# Sheet5.net
KiCad netlist of a schematic drawn in Altium Designer
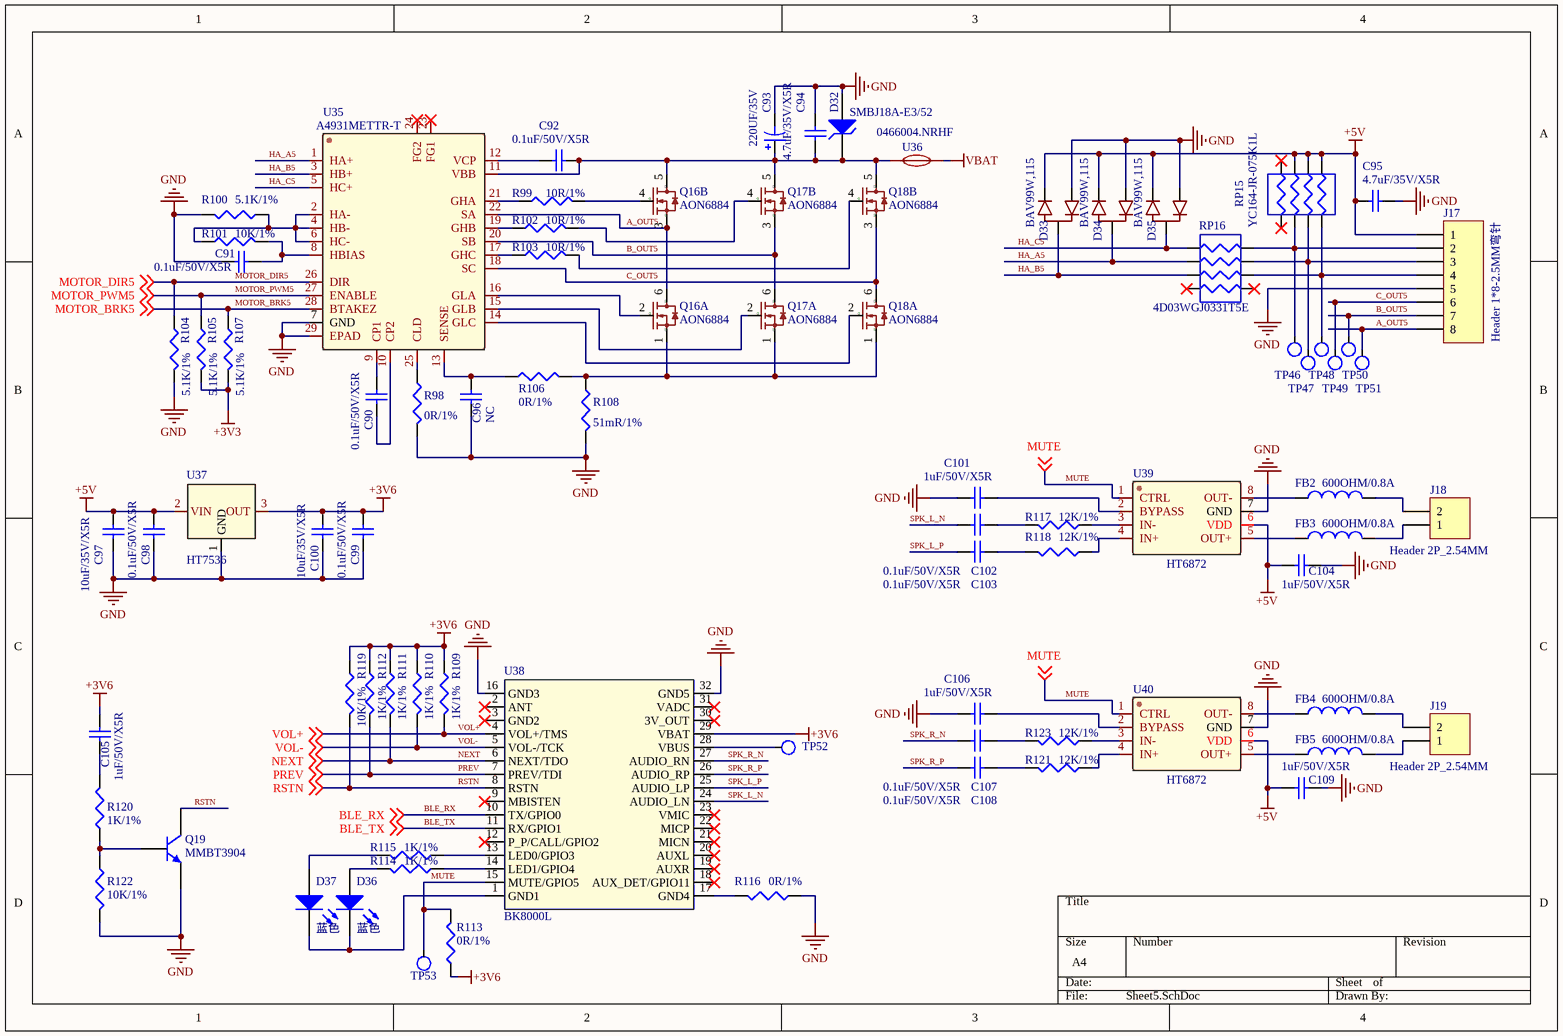
[diagram p0: Sheet5.SchDoc]

(export (version "E")
  (design (tool "Eeschema 10.0.6"))
  (components
    (comp (ref "C90")
      (value "0.1uF/50V/X5R")
      (footprint "C0603")
      (description "Capacitor (Semiconductor SIM Model)")
      (fields (field (name "PUBLISHER") "Altium Limited"))
      (libsource (lib "Miscellaneous Devices") (part "Cap Semi"))
    )
    (comp (ref "C91")
      (value "0.1uF/50V/X5R")
      (footprint "C0603")
      (description "Capacitor (Semiconductor SIM Model)")
      (fields (field (name "PUBLISHER") "Altium Limited"))
      (libsource (lib "Miscellaneous Devices") (part "Cap Semi"))
    )
    (comp (ref "C92")
      (value "0.1uF/50V/X5R")
      (footprint "C0603")
      (description "Capacitor (Semiconductor SIM Model)")
      (fields (field (name "PUBLISHER") "Altium Limited"))
      (libsource (lib "Miscellaneous Devices") (part "Cap Semi"))
    )
    (comp (ref "C93")
      (value "220UF/35V")
      (footprint "SMD_8X10.2")
      (description "Polarized Capacitor (Radial)")
      (fields (field (name "PUBLISHER") "Altium Limited"))
      (libsource (lib "Miscellaneous Devices") (part "Cap Pol1"))
    )
    (comp (ref "C94")
      (value "4.7uF/35V/X5R")
      (footprint "C0805")
      (description "Capacitor (Semiconductor SIM Model)")
      (fields (field (name "PUBLISHER") "Altium Limited"))
      (libsource (lib "Miscellaneous Devices") (part "Cap Semi"))
    )
    (comp (ref "C95")
      (value "4.7uF/35V/X5R")
      (footprint "C0603")
      (description "Capacitor (Semiconductor SIM Model)")
      (fields (field (name "PUBLISHER") "Altium Limited"))
      (libsource (lib "Miscellaneous Devices") (part "Cap Semi"))
    )
    (comp (ref "C96")
      (value "NC")
      (footprint "C0603")
      (description "Capacitor (Semiconductor SIM Model)")
      (fields (field (name "PUBLISHER") "Altium Limited"))
      (libsource (lib "Miscellaneous Devices") (part "Cap Semi"))
    )
    (comp (ref "C97")
      (value "10uF/35V/X5R")
      (footprint "C0805")
      (description "Capacitor (Semiconductor SIM Model)")
      (fields (field (name "PUBLISHER") "Altium Limited"))
      (libsource (lib "Miscellaneous Devices") (part "Cap Semi"))
    )
    (comp (ref "C98")
      (value "0.1uF/50V/X5R")
      (footprint "C0603")
      (description "Capacitor (Semiconductor SIM Model)")
      (fields (field (name "PUBLISHER") "Altium Limited"))
      (libsource (lib "Miscellaneous Devices") (part "Cap Semi"))
    )
    (comp (ref "C99")
      (value "0.1uF/50V/X5R")
      (footprint "C0603")
      (description "Capacitor (Semiconductor SIM Model)")
      (fields (field (name "PUBLISHER") "Altium Limited"))
      (libsource (lib "Miscellaneous Devices") (part "Cap Semi"))
    )
    (comp (ref "C100")
      (value "10uF/35V/X5R")
      (footprint "C0805")
      (description "Capacitor (Semiconductor SIM Model)")
      (fields (field (name "PUBLISHER") "Altium Limited"))
      (libsource (lib "Miscellaneous Devices") (part "Cap Semi"))
    )
    (comp (ref "C101")
      (value "1uF/50V/X5R")
      (footprint "C0603")
      (description "Capacitor (Semiconductor SIM Model)")
      (fields (field (name "PUBLISHER") "Altium Limited"))
      (libsource (lib "Miscellaneous Devices") (part "Cap Semi"))
    )
    (comp (ref "C102")
      (value "0.1uF/50V/X5R")
      (footprint "C0603")
      (description "Capacitor (Semiconductor SIM Model)")
      (fields (field (name "PUBLISHER") "Altium Limited"))
      (libsource (lib "Miscellaneous Devices") (part "Cap Semi"))
    )
    (comp (ref "C103")
      (value "0.1uF/50V/X5R")
      (footprint "C0603")
      (description "Capacitor (Semiconductor SIM Model)")
      (fields (field (name "PUBLISHER") "Altium Limited"))
      (libsource (lib "Miscellaneous Devices") (part "Cap Semi"))
    )
    (comp (ref "C104")
      (value "1uF/50V/X5R")
      (footprint "C0603")
      (description "Capacitor (Semiconductor SIM Model)")
      (fields (field (name "PUBLISHER") "Altium Limited"))
      (libsource (lib "Miscellaneous Devices") (part "Cap Semi"))
    )
    (comp (ref "C105")
      (value "1uF/50V/X5R")
      (footprint "C0603")
      (description "Capacitor (Semiconductor SIM Model)")
      (fields (field (name "PUBLISHER") "Altium Limited"))
      (libsource (lib "Miscellaneous Devices") (part "Cap Semi"))
    )
    (comp (ref "C106")
      (value "1uF/50V/X5R")
      (footprint "C0603")
      (description "Capacitor (Semiconductor SIM Model)")
      (fields (field (name "PUBLISHER") "Altium Limited"))
      (libsource (lib "Miscellaneous Devices") (part "Cap Semi"))
    )
    (comp (ref "C107")
      (value "0.1uF/50V/X5R")
      (footprint "C0603")
      (description "Capacitor (Semiconductor SIM Model)")
      (fields (field (name "PUBLISHER") "Altium Limited"))
      (libsource (lib "Miscellaneous Devices") (part "Cap Semi"))
    )
    (comp (ref "C108")
      (value "0.1uF/50V/X5R")
      (footprint "C0603")
      (description "Capacitor (Semiconductor SIM Model)")
      (fields (field (name "PUBLISHER") "Altium Limited"))
      (libsource (lib "Miscellaneous Devices") (part "Cap Semi"))
    )
    (comp (ref "C109")
      (value "1uF/50V/X5R")
      (footprint "C0603")
      (description "Capacitor (Semiconductor SIM Model)")
      (fields (field (name "PUBLISHER") "Altium Limited"))
      (libsource (lib "Miscellaneous Devices") (part "Cap Semi"))
    )
    (comp (ref "D32")
      (value "SMBJ18A-E3/52")
      (footprint "SMB")
      (description "Zener Diode")
      (fields (field (name "PUBLISHER") "Altium Limited"))
      (libsource (lib "Miscellaneous Devices") (part "D Zener"))
    )
    (comp (ref "D33") (value "BAV99W,115") (libsource (lib "Schlib1") (part "BAV99W,115")))
    (comp (ref "D34") (value "BAV99W,115") (libsource (lib "Schlib1") (part "BAV99W,115")))
    (comp (ref "D35") (value "BAV99W,115") (libsource (lib "Schlib1") (part "BAV99W,115")))
    (comp (ref "D36")
      (value "蓝色")
      (footprint "LED0603")
      (description "Typical RED, GREEN, YELLOW, AMBER GaAs LED")
      (fields (field (name "PUBLISHER") "Altium Limited"))
      (libsource (lib "Miscellaneous Devices") (part "LED2"))
    )
    (comp (ref "D37")
      (value "蓝色")
      (footprint "LED0603")
      (description "Typical RED, GREEN, YELLOW, AMBER GaAs LED")
      (fields (field (name "PUBLISHER") "Altium Limited"))
      (libsource (lib "Miscellaneous Devices") (part "LED2"))
    )
    (comp (ref "FB2")
      (value "600OHM/0.8A")
      (footprint "FB0805")
      (description "Inductor")
      (fields (field (name "PUBLISHER") "Altium Limited"))
      (libsource (lib "Miscellaneous Devices") (part "Inductor"))
    )
    (comp (ref "FB3")
      (value "600OHM/0.8A")
      (footprint "FB0805")
      (description "Inductor")
      (fields (field (name "PUBLISHER") "Altium Limited"))
      (libsource (lib "Miscellaneous Devices") (part "Inductor"))
    )
    (comp (ref "FB4")
      (value "600OHM/0.8A")
      (footprint "FB0805")
      (description "Inductor")
      (fields (field (name "PUBLISHER") "Altium Limited"))
      (libsource (lib "Miscellaneous Devices") (part "Inductor"))
    )
    (comp (ref "FB5")
      (value "600OHM/0.8A")
      (footprint "FB0805")
      (description "Inductor")
      (fields (field (name "PUBLISHER") "Altium Limited"))
      (libsource (lib "Miscellaneous Devices") (part "Inductor"))
    )
    (comp (ref "J17")
      (value "Header 1*8-2.5MM弯针")
      (footprint "DIP_8X2.5")
      (description "Header, 8-Pin")
      (fields (field (name "PUBLISHER") "Altium Limited"))
      (libsource (lib "Miscellaneous Connectors") (part "Header 8"))
    )
    (comp (ref "J18")
      (value "Header 2P_2.54MM")
      (footprint "DIP_2X2.54")
      (description "Header, 2-Pin")
      (fields (field (name "PUBLISHER") "Altium Limited"))
      (libsource (lib "Miscellaneous Connectors") (part "Header 2"))
    )
    (comp (ref "J19")
      (value "Header 2P_2.54MM")
      (footprint "DIP_2X2.54")
      (description "Header, 2-Pin")
      (fields (field (name "PUBLISHER") "Altium Limited"))
      (libsource (lib "Miscellaneous Connectors") (part "Header 2"))
    )
    (comp (ref "Q16") (value "AON6884") (footprint "AOS") (libsource (lib "Schlib1") (part "AON6884")))
    (comp (ref "Q17") (value "AON6884") (footprint "AOS") (libsource (lib "Schlib1") (part "AON6884")))
    (comp (ref "Q18") (value "AON6884") (footprint "AOS") (libsource (lib "Schlib1") (part "AON6884")))
    (comp (ref "Q19") (value "MMBT3904") (footprint "SOT-23") (libsource (lib "Schlib1") (part "MMBT3904")))
    (comp (ref "R98")
      (value "0R/1%")
      (footprint "R0603")
      (description "Resistor")
      (fields (field (name "PUBLISHER") "Altium Limited"))
      (libsource (lib "Miscellaneous Devices") (part "Res3"))
    )
    (comp (ref "R99")
      (value "10R/1%")
      (footprint "R0603")
      (description "Resistor")
      (fields (field (name "PUBLISHER") "Altium Limited"))
      (libsource (lib "Miscellaneous Devices") (part "Res3"))
    )
    (comp (ref "R100")
      (value "5.1K/1%")
      (footprint "R0603")
      (description "Resistor")
      (fields (field (name "PUBLISHER") "Altium Limited"))
      (libsource (lib "Miscellaneous Devices") (part "Res3"))
    )
    (comp (ref "R101")
      (value "10K/1%")
      (footprint "R0603")
      (description "Resistor")
      (fields (field (name "PUBLISHER") "Altium Limited"))
      (libsource (lib "Miscellaneous Devices") (part "Res3"))
    )
    (comp (ref "R102")
      (value "10R/1%")
      (footprint "R0603")
      (description "Resistor")
      (fields (field (name "PUBLISHER") "Altium Limited"))
      (libsource (lib "Miscellaneous Devices") (part "Res3"))
    )
    (comp (ref "R103")
      (value "10R/1%")
      (footprint "R0603")
      (description "Resistor")
      (fields (field (name "PUBLISHER") "Altium Limited"))
      (libsource (lib "Miscellaneous Devices") (part "Res3"))
    )
    (comp (ref "R104")
      (value "5.1K/1%")
      (footprint "R0603")
      (description "Resistor")
      (fields (field (name "PUBLISHER") "Altium Limited"))
      (libsource (lib "Miscellaneous Devices") (part "Res3"))
    )
    (comp (ref "R105")
      (value "5.1K/1%")
      (footprint "R0603")
      (description "Resistor")
      (fields (field (name "PUBLISHER") "Altium Limited"))
      (libsource (lib "Miscellaneous Devices") (part "Res3"))
    )
    (comp (ref "R106")
      (value "0R/1%")
      (footprint "R0603")
      (description "Resistor")
      (fields (field (name "PUBLISHER") "Altium Limited"))
      (libsource (lib "Miscellaneous Devices") (part "Res3"))
    )
    (comp (ref "R107")
      (value "5.1K/1%")
      (footprint "R0603")
      (description "Resistor")
      (fields (field (name "PUBLISHER") "Altium Limited"))
      (libsource (lib "Miscellaneous Devices") (part "Res3"))
    )
    (comp (ref "R108")
      (value "51mR/1%")
      (footprint "R0805")
      (description "Resistor")
      (fields (field (name "PUBLISHER") "Altium Limited"))
      (libsource (lib "Miscellaneous Devices") (part "Res3"))
    )
    (comp (ref "R109")
      (value "1K/1%")
      (footprint "R0603")
      (description "Resistor")
      (fields (field (name "PUBLISHER") "Altium Limited"))
      (libsource (lib "Miscellaneous Devices") (part "Res3"))
    )
    (comp (ref "R110")
      (value "1K/1%")
      (footprint "R0603")
      (description "Resistor")
      (fields (field (name "PUBLISHER") "Altium Limited"))
      (libsource (lib "Miscellaneous Devices") (part "Res3"))
    )
    (comp (ref "R111")
      (value "1K/1%")
      (footprint "R0603")
      (description "Resistor")
      (fields (field (name "PUBLISHER") "Altium Limited"))
      (libsource (lib "Miscellaneous Devices") (part "Res3"))
    )
    (comp (ref "R112")
      (value "1K/1%")
      (footprint "R0603")
      (description "Resistor")
      (fields (field (name "PUBLISHER") "Altium Limited"))
      (libsource (lib "Miscellaneous Devices") (part "Res3"))
    )
    (comp (ref "R113")
      (value "0R/1%")
      (footprint "R0603")
      (description "Resistor")
      (fields (field (name "PUBLISHER") "Altium Limited"))
      (libsource (lib "Miscellaneous Devices") (part "Res3"))
    )
    (comp (ref "R114")
      (value "1K/1%")
      (footprint "R0603")
      (description "Resistor")
      (fields (field (name "PUBLISHER") "Altium Limited"))
      (libsource (lib "Miscellaneous Devices") (part "Res3"))
    )
    (comp (ref "R115")
      (value "1K/1%")
      (footprint "R0603")
      (description "Resistor")
      (fields (field (name "PUBLISHER") "Altium Limited"))
      (libsource (lib "Miscellaneous Devices") (part "Res3"))
    )
    (comp (ref "R116")
      (value "0R/1%")
      (footprint "R0603")
      (description "Resistor")
      (fields (field (name "PUBLISHER") "Altium Limited"))
      (libsource (lib "Miscellaneous Devices") (part "Res3"))
    )
    (comp (ref "R117")
      (value "12K/1%")
      (footprint "R0603")
      (description "Resistor")
      (fields (field (name "PUBLISHER") "Altium Limited"))
      (libsource (lib "Miscellaneous Devices") (part "Res3"))
    )
    (comp (ref "R118")
      (value "12K/1%")
      (footprint "R0603")
      (description "Resistor")
      (fields (field (name "PUBLISHER") "Altium Limited"))
      (libsource (lib "Miscellaneous Devices") (part "Res3"))
    )
    (comp (ref "R119")
      (value "10K/1%")
      (footprint "R0603")
      (description "Resistor")
      (fields (field (name "PUBLISHER") "Altium Limited"))
      (libsource (lib "Miscellaneous Devices") (part "Res3"))
    )
    (comp (ref "R120")
      (value "1K/1%")
      (footprint "R0603")
      (description "Resistor")
      (fields (field (name "PUBLISHER") "Altium Limited"))
      (libsource (lib "Miscellaneous Devices") (part "Res3"))
    )
    (comp (ref "R121")
      (value "12K/1%")
      (footprint "R0603")
      (description "Resistor")
      (fields (field (name "PUBLISHER") "Altium Limited"))
      (libsource (lib "Miscellaneous Devices") (part "Res3"))
    )
    (comp (ref "R122")
      (value "10K/1%")
      (footprint "R0603")
      (description "Resistor")
      (fields (field (name "PUBLISHER") "Altium Limited"))
      (libsource (lib "Miscellaneous Devices") (part "Res3"))
    )
    (comp (ref "R123")
      (value "12K/1%")
      (footprint "R0603")
      (description "Resistor")
      (fields (field (name "PUBLISHER") "Altium Limited"))
      (libsource (lib "Miscellaneous Devices") (part "Res3"))
    )
    (comp (ref "RP15")
      (value "YC164-JR-075K1L")
      (footprint "RP-1206")
      (libsource (lib "Schlib1") (part "RP"))
    )
    (comp (ref "RP16") (value "4D03WGJ0331T5E") (footprint "RP-1206") (libsource (lib "Schlib1") (part "RP")))
    (comp (ref "TP46") (value "TP") (footprint "TP") (libsource (lib "Schlib1") (part "TP")))
    (comp (ref "TP47") (value "TP") (footprint "TP") (libsource (lib "Schlib1") (part "TP")))
    (comp (ref "TP48") (value "TP") (footprint "TP") (libsource (lib "Schlib1") (part "TP")))
    (comp (ref "TP49") (value "TP") (footprint "TP") (libsource (lib "Schlib1") (part "TP")))
    (comp (ref "TP50") (value "TP") (footprint "TP") (libsource (lib "Schlib1") (part "TP")))
    (comp (ref "TP51") (value "TP") (footprint "TP") (libsource (lib "Schlib1") (part "TP")))
    (comp (ref "TP52") (value "TP") (footprint "TP") (libsource (lib "Schlib1") (part "TP")))
    (comp (ref "TP53") (value "TP") (footprint "TP") (libsource (lib "Schlib1") (part "TP")))
    (comp (ref "U35")
      (value "A4931METTR-T")
      (footprint "QFN-28")
      (libsource (lib "Schlib1") (part "A4931METTR-T"))
    )
    (comp (ref "U36")
      (value "0466004.NRHF")
      (footprint "1206")
      (libsource (lib "Schlib1") (part "0466004.NRHF"))
    )
    (comp (ref "U37") (value "HT7536") (libsource (lib "Schlib1") (part "HT7536")))
    (comp (ref "U38") (value "BK8000L") (footprint "BT") (libsource (lib "Schlib1") (part "BK8000L")))
    (comp (ref "U39") (value "HT6872") (footprint "SOIC-8") (libsource (lib "Schlib1") (part "HT6872")))
    (comp (ref "U40") (value "HT6872") (footprint "SOIC-8") (libsource (lib "Schlib1") (part "HT6872")))
  )
  (nets
    (net (code "1") (name "+3V3") (class "Default")
      (node (ref "R105") (pin "2") (pinfunction "2_2") (pintype "passive"))
      (node (ref "R107") (pin "2") (pinfunction "2_2") (pintype "passive"))
    )
    (net (code "2") (name "+3V6") (class "Default")
      (node (ref "C100") (pin "1") (pinfunction "1_1") (pintype "passive"))
      (node (ref "C105") (pin "1") (pinfunction "1_1") (pintype "passive"))
      (node (ref "C99") (pin "1") (pinfunction "1_1") (pintype "passive"))
      (node (ref "R109") (pin "1") (pinfunction "1_1") (pintype "passive"))
      (node (ref "R110") (pin "1") (pinfunction "1_1") (pintype "passive"))
      (node (ref "R111") (pin "1") (pinfunction "1_1") (pintype "passive"))
      (node (ref "R112") (pin "1") (pinfunction "1_1") (pintype "passive"))
      (node (ref "R113") (pin "1") (pinfunction "1_1") (pintype "passive"))
      (node (ref "R119") (pin "1") (pinfunction "1_1") (pintype "passive"))
      (node (ref "U37") (pin "3") (pinfunction "OUT_3") (pintype "passive"))
      (node (ref "U38") (pin "29") (pinfunction "VBAT_29") (pintype "passive"))
    )
    (net (code "3") (name "+5V") (class "Default")
      (node (ref "C104") (pin "2") (pinfunction "2_2") (pintype "passive"))
      (node (ref "C109") (pin "1") (pinfunction "1_1") (pintype "passive"))
      (node (ref "C95") (pin "1") (pinfunction "1_1") (pintype "passive"))
      (node (ref "C97") (pin "2") (pinfunction "2_2") (pintype "passive"))
      (node (ref "C98") (pin "2") (pinfunction "2_2") (pintype "passive"))
      (node (ref "D33") (pin "2") (pinfunction "2_2") (pintype "passive"))
      (node (ref "D34") (pin "2") (pinfunction "2_2") (pintype "passive"))
      (node (ref "D35") (pin "2") (pinfunction "2_2") (pintype "passive"))
      (node (ref "J17") (pin "1") (pinfunction "1_1") (pintype "passive"))
      (node (ref "RP15") (pin "1") (pinfunction "1_1") (pintype "passive"))
      (node (ref "RP15") (pin "2") (pinfunction "2_2") (pintype "passive"))
      (node (ref "RP15") (pin "3") (pinfunction "3_3") (pintype "passive"))
      (node (ref "U37") (pin "2") (pinfunction "VIN_2") (pintype "passive"))
      (node (ref "U39") (pin "6") (pinfunction "VDD_6") (pintype "passive"))
      (node (ref "U40") (pin "6") (pinfunction "VDD_6") (pintype "passive"))
    )
    (net (code "4") (name "/A_OUT5") (class "Default")
      (node (ref "J17") (pin "8") (pinfunction "8_8") (pintype "passive"))
      (node (ref "Q16") (pin "3") (pinfunction "S_3") (pintype "passive"))
      (node (ref "Q16") (pin "6") (pinfunction "6_6") (pintype "passive"))
      (node (ref "TP51") (pin "1") (pinfunction "1_1") (pintype "passive"))
      (node (ref "U35") (pin "22") (pinfunction "SA_22") (pintype "passive"))
    )
    (net (code "5") (name "/B_OUT5") (class "Default")
      (node (ref "J17") (pin "7") (pinfunction "7_7") (pintype "passive"))
      (node (ref "Q17") (pin "3") (pinfunction "S_3") (pintype "passive"))
      (node (ref "Q17") (pin "6") (pinfunction "6_6") (pintype "passive"))
      (node (ref "TP50") (pin "1") (pinfunction "1_1") (pintype "passive"))
      (node (ref "U35") (pin "20") (pinfunction "SB_20") (pintype "passive"))
    )
    (net (code "6") (name "/C_OUT5") (class "Default")
      (node (ref "J17") (pin "6") (pinfunction "6_6") (pintype "passive"))
      (node (ref "Q18") (pin "3") (pinfunction "S_3") (pintype "passive"))
      (node (ref "Q18") (pin "6") (pinfunction "6_6") (pintype "passive"))
      (node (ref "TP49") (pin "1") (pinfunction "1_1") (pintype "passive"))
      (node (ref "U35") (pin "18") (pinfunction "SC_18") (pintype "passive"))
    )
    (net (code "7") (name "/HA_A5") (class "Default")
      (node (ref "D34") (pin "3") (pinfunction "3_3") (pintype "passive"))
      (node (ref "RP16") (pin "2") (pinfunction "2_2") (pintype "passive"))
      (node (ref "U35") (pin "1") (pinfunction "HA+_1") (pintype "passive"))
    )
    (net (code "8") (name "/HA_B5") (class "Default")
      (node (ref "D33") (pin "3") (pinfunction "3_3") (pintype "passive"))
      (node (ref "RP16") (pin "3") (pinfunction "3_3") (pintype "passive"))
      (node (ref "U35") (pin "3") (pinfunction "HB+_3") (pintype "passive"))
    )
    (net (code "9") (name "/HA_C5") (class "Default")
      (node (ref "D35") (pin "3") (pinfunction "3_3") (pintype "passive"))
      (node (ref "RP16") (pin "1") (pinfunction "1_1") (pintype "passive"))
      (node (ref "U35") (pin "5") (pinfunction "HC+_5") (pintype "passive"))
    )
    (net (code "10") (name "/SPK_L_N") (class "Default")
      (node (ref "C102") (pin "1") (pinfunction "1_1") (pintype "passive"))
      (node (ref "U38") (pin "24") (pinfunction "AUDIO_LN_24") (pintype "passive"))
    )
    (net (code "11") (name "/SPK_L_P") (class "Default")
      (node (ref "C103") (pin "1") (pinfunction "1_1") (pintype "passive"))
      (node (ref "U38") (pin "25") (pinfunction "AUDIO_LP_25") (pintype "passive"))
    )
    (net (code "12") (name "/SPK_R_N") (class "Default")
      (node (ref "C107") (pin "2") (pinfunction "2_2") (pintype "passive"))
      (node (ref "U38") (pin "27") (pinfunction "AUDIO_RN_27") (pintype "passive"))
    )
    (net (code "13") (name "/SPK_R_P") (class "Default")
      (node (ref "C108") (pin "2") (pinfunction "2_2") (pintype "passive"))
      (node (ref "U38") (pin "26") (pinfunction "AUDIO_RP_26") (pintype "passive"))
    )
    (net (code "14") (name "BLE_RX") (class "Default")
      (node (ref "U38") (pin "10") (pinfunction "TX/GPIO0_10") (pintype "passive"))
    )
    (net (code "15") (name "BLE_TX") (class "Default")
      (node (ref "U38") (pin "11") (pinfunction "RX/GPIO1_11") (pintype "passive"))
    )
    (net (code "16") (name "GND") (class "Default")
      (node (ref "C100") (pin "2") (pinfunction "2_2") (pintype "passive"))
      (node (ref "C101") (pin "2") (pinfunction "2_2") (pintype "passive"))
      (node (ref "C104") (pin "1") (pinfunction "1_1") (pintype "passive"))
      (node (ref "C106") (pin "2") (pinfunction "2_2") (pintype "passive"))
      (node (ref "C109") (pin "2") (pinfunction "2_2") (pintype "passive"))
      (node (ref "C91") (pin "1") (pinfunction "1_1") (pintype "passive"))
      (node (ref "C93") (pin "2") (pinfunction "2_2") (pintype "passive"))
      (node (ref "C94") (pin "2") (pinfunction "2_2") (pintype "passive"))
      (node (ref "C95") (pin "2") (pinfunction "2_2") (pintype "passive"))
      (node (ref "C96") (pin "2") (pinfunction "2_2") (pintype "passive"))
      (node (ref "C97") (pin "1") (pinfunction "1_1") (pintype "passive"))
      (node (ref "C98") (pin "1") (pinfunction "1_1") (pintype "passive"))
      (node (ref "C99") (pin "2") (pinfunction "2_2") (pintype "passive"))
      (node (ref "D32") (pin "1") (pinfunction "A_1") (pintype "passive"))
      (node (ref "D33") (pin "1") (pinfunction "1_1") (pintype "passive"))
      (node (ref "D34") (pin "1") (pinfunction "1_1") (pintype "passive"))
      (node (ref "D35") (pin "1") (pinfunction "1_1") (pintype "passive"))
      (node (ref "J17") (pin "5") (pinfunction "5_5") (pintype "passive"))
      (node (ref "Q19") (pin "2") (pinfunction "E_2") (pintype "passive"))
      (node (ref "R100") (pin "2") (pinfunction "2_2") (pintype "passive"))
      (node (ref "R104") (pin "2") (pinfunction "2_2") (pintype "passive"))
      (node (ref "R108") (pin "2") (pinfunction "2_2") (pintype "passive"))
      (node (ref "R116") (pin "1") (pinfunction "1_1") (pintype "passive"))
      (node (ref "R122") (pin "2") (pinfunction "2_2") (pintype "passive"))
      (node (ref "R98") (pin "2") (pinfunction "2_2") (pintype "passive"))
      (node (ref "U35") (pin "29") (pinfunction "EPAD_29") (pintype "passive"))
      (node (ref "U35") (pin "7") (pinfunction "GND_7") (pintype "passive"))
      (node (ref "U37") (pin "1") (pinfunction "GND_1") (pintype "passive"))
      (node (ref "U38") (pin "16") (pinfunction "GND3_16") (pintype "passive"))
      (node (ref "U38") (pin "32") (pinfunction "GND5_32") (pintype "passive"))
      (node (ref "U39") (pin "7") (pinfunction "GND_7") (pintype "passive"))
      (node (ref "U40") (pin "7") (pinfunction "GND_7") (pintype "passive"))
    )
    (net (code "17") (name "MOTOR_BRK5") (class "Default")
      (node (ref "R107") (pin "1") (pinfunction "1_1") (pintype "passive"))
      (node (ref "U35") (pin "28") (pinfunction "BTAKEZ_28") (pintype "passive"))
    )
    (net (code "18") (name "MOTOR_DIR5") (class "Default")
      (node (ref "R104") (pin "1") (pinfunction "1_1") (pintype "passive"))
      (node (ref "U35") (pin "26") (pinfunction "DIR_26") (pintype "passive"))
    )
    (net (code "19") (name "MOTOR_PWM5") (class "Default")
      (node (ref "R105") (pin "1") (pinfunction "1_1") (pintype "passive"))
      (node (ref "U35") (pin "27") (pinfunction "ENABLE_27") (pintype "passive"))
    )
    (net (code "20") (name "MUTE") (class "Default")
      (node (ref "R113") (pin "2") (pinfunction "2_2") (pintype "passive"))
      (node (ref "TP53") (pin "1") (pinfunction "1_1") (pintype "passive"))
      (node (ref "U38") (pin "15") (pinfunction "MUTE/GPIO5_15") (pintype "passive"))
      (node (ref "U39") (pin "1") (pinfunction "CTRL_1") (pintype "passive"))
      (node (ref "U40") (pin "1") (pinfunction "CTRL_1") (pintype "passive"))
    )
    (net (code "21") (name "NEXT") (class "Default")
      (node (ref "R111") (pin "2") (pinfunction "2_2") (pintype "passive"))
      (node (ref "U38") (pin "6") (pinfunction "NEXT/TDO_6") (pintype "passive"))
    )
    (net (code "22") (name "Net-(C102-Pad2)") (class "Default")
      (node (ref "C102") (pin "2") (pinfunction "2_2") (pintype "passive"))
      (node (ref "R117") (pin "2") (pinfunction "2_2") (pintype "passive"))
    )
    (net (code "23") (name "Net-(C103-Pad2)") (class "Default")
      (node (ref "C103") (pin "2") (pinfunction "2_2") (pintype "passive"))
      (node (ref "R118") (pin "2") (pinfunction "2_2") (pintype "passive"))
    )
    (net (code "24") (name "Net-(C105-Pad2)") (class "Default")
      (node (ref "C105") (pin "2") (pinfunction "2_2") (pintype "passive"))
      (node (ref "R120") (pin "2") (pinfunction "2_2") (pintype "passive"))
    )
    (net (code "25") (name "Net-(C107-Pad1)") (class "Default")
      (node (ref "C107") (pin "1") (pinfunction "1_1") (pintype "passive"))
      (node (ref "R123") (pin "2") (pinfunction "2_2") (pintype "passive"))
    )
    (net (code "26") (name "Net-(C108-Pad1)") (class "Default")
      (node (ref "C108") (pin "1") (pinfunction "1_1") (pintype "passive"))
      (node (ref "R121") (pin "2") (pinfunction "2_2") (pintype "passive"))
    )
    (net (code "27") (name "Net-(D32-K)") (class "Default")
      (node (ref "C92") (pin "2") (pinfunction "2_2") (pintype "passive"))
      (node (ref "C93") (pin "1") (pinfunction "1_1") (pintype "passive"))
      (node (ref "C94") (pin "1") (pinfunction "1_1") (pintype "passive"))
      (node (ref "D32") (pin "2") (pinfunction "K_2") (pintype "passive"))
      (node (ref "Q16") (pin "5") (pinfunction "D_5") (pintype "passive"))
      (node (ref "Q17") (pin "5") (pinfunction "D_5") (pintype "passive"))
      (node (ref "Q18") (pin "5") (pinfunction "D_5") (pintype "passive"))
      (node (ref "U35") (pin "11") (pinfunction "VBB_11") (pintype "passive"))
      (node (ref "U36") (pin "1") (pinfunction "1_1") (pintype "passive"))
    )
    (net (code "28") (name "Net-(D36-A)") (class "Default")
      (node (ref "D36") (pin "1") (pinfunction "A_1") (pintype "passive"))
      (node (ref "R114") (pin "2") (pinfunction "2_2") (pintype "passive"))
    )
    (net (code "29") (name "Net-(D36-K)") (class "Default")
      (node (ref "D36") (pin "2") (pinfunction "K_2") (pintype "passive"))
      (node (ref "D37") (pin "2") (pinfunction "K_2") (pintype "passive"))
      (node (ref "U38") (pin "1") (pinfunction "GND1_1") (pintype "passive"))
    )
    (net (code "30") (name "Net-(D37-A)") (class "Default")
      (node (ref "D37") (pin "1") (pinfunction "A_1") (pintype "passive"))
      (node (ref "R115") (pin "2") (pinfunction "2_2") (pintype "passive"))
    )
    (net (code "31") (name "Net-(FB2-Pad2)") (class "Default")
      (node (ref "FB2") (pin "2") (pinfunction "2_2") (pintype "passive"))
      (node (ref "J18") (pin "2") (pinfunction "2_2") (pintype "passive"))
    )
    (net (code "32") (name "Net-(FB3-Pad2)") (class "Default")
      (node (ref "FB3") (pin "2") (pinfunction "2_2") (pintype "passive"))
      (node (ref "J18") (pin "1") (pinfunction "1_1") (pintype "passive"))
    )
    (net (code "33") (name "Net-(FB4-Pad2)") (class "Default")
      (node (ref "FB4") (pin "2") (pinfunction "2_2") (pintype "passive"))
      (node (ref "J19") (pin "2") (pinfunction "2_2") (pintype "passive"))
    )
    (net (code "34") (name "Net-(FB5-Pad2)") (class "Default")
      (node (ref "FB5") (pin "2") (pinfunction "2_2") (pintype "passive"))
      (node (ref "J19") (pin "1") (pinfunction "1_1") (pintype "passive"))
    )
    (net (code "35") (name "Net-(J17-Pad2)") (class "Default")
      (node (ref "J17") (pin "2") (pinfunction "2_2") (pintype "passive"))
      (node (ref "RP15") (pin "6") (pinfunction "6_6") (pintype "passive"))
      (node (ref "RP16") (pin "8") (pinfunction "8_8") (pintype "passive"))
      (node (ref "TP46") (pin "1") (pinfunction "1_1") (pintype "passive"))
    )
    (net (code "36") (name "Net-(J17-Pad3)") (class "Default")
      (node (ref "J17") (pin "3") (pinfunction "3_3") (pintype "passive"))
      (node (ref "RP15") (pin "7") (pinfunction "7_7") (pintype "passive"))
      (node (ref "RP16") (pin "7") (pinfunction "7_7") (pintype "passive"))
      (node (ref "TP47") (pin "1") (pinfunction "1_1") (pintype "passive"))
    )
    (net (code "37") (name "Net-(J17-Pad4)") (class "Default")
      (node (ref "J17") (pin "4") (pinfunction "4_4") (pintype "passive"))
      (node (ref "RP15") (pin "8") (pinfunction "8_8") (pintype "passive"))
      (node (ref "RP16") (pin "6") (pinfunction "6_6") (pintype "passive"))
      (node (ref "TP48") (pin "1") (pinfunction "1_1") (pintype "passive"))
    )
    (net (code "38") (name "Net-(Q16A-G)") (class "Default")
      (node (ref "Q16") (pin "2") (pinfunction "G_2") (pintype "passive"))
      (node (ref "U35") (pin "16") (pinfunction "GLA_16") (pintype "passive"))
    )
    (net (code "39") (name "Net-(Q16A-S)") (class "Default")
      (node (ref "Q16") (pin "1") (pinfunction "S_1") (pintype "passive"))
      (node (ref "Q17") (pin "1") (pinfunction "S_1") (pintype "passive"))
      (node (ref "Q18") (pin "1") (pinfunction "S_1") (pintype "passive"))
      (node (ref "R106") (pin "2") (pinfunction "2_2") (pintype "passive"))
      (node (ref "R108") (pin "1") (pinfunction "1_1") (pintype "passive"))
    )
    (net (code "40") (name "Net-(Q16B-G)") (class "Default")
      (node (ref "Q16") (pin "4") (pinfunction "G_4") (pintype "passive"))
      (node (ref "R99") (pin "2") (pinfunction "2_2") (pintype "passive"))
    )
    (net (code "41") (name "Net-(Q17A-G)") (class "Default")
      (node (ref "Q17") (pin "2") (pinfunction "G_2") (pintype "passive"))
      (node (ref "U35") (pin "15") (pinfunction "GLB_15") (pintype "passive"))
    )
    (net (code "42") (name "Net-(Q17B-G)") (class "Default")
      (node (ref "Q17") (pin "4") (pinfunction "G_4") (pintype "passive"))
      (node (ref "R102") (pin "2") (pinfunction "2_2") (pintype "passive"))
    )
    (net (code "43") (name "Net-(Q18A-G)") (class "Default")
      (node (ref "Q18") (pin "2") (pinfunction "G_2") (pintype "passive"))
      (node (ref "U35") (pin "14") (pinfunction "GLC_14") (pintype "passive"))
    )
    (net (code "44") (name "Net-(Q18B-G)") (class "Default")
      (node (ref "Q18") (pin "4") (pinfunction "G_4") (pintype "passive"))
      (node (ref "R103") (pin "2") (pinfunction "2_2") (pintype "passive"))
    )
    (net (code "45") (name "Net-(Q19-B)") (class "Default")
      (node (ref "Q19") (pin "1") (pinfunction "B_1") (pintype "passive"))
      (node (ref "R120") (pin "1") (pinfunction "1_1") (pintype "passive"))
      (node (ref "R122") (pin "1") (pinfunction "1_1") (pintype "passive"))
    )
    (net (code "46") (name "Net-(U35-CLD)") (class "Default")
      (node (ref "R98") (pin "1") (pinfunction "1_1") (pintype "passive"))
      (node (ref "U35") (pin "25") (pinfunction "CLD_25") (pintype "passive"))
    )
    (net (code "47") (name "Net-(U35-CP1)") (class "Default")
      (node (ref "C90") (pin "1") (pinfunction "1_1") (pintype "passive"))
      (node (ref "U35") (pin "9") (pinfunction "CP1_9") (pintype "passive"))
    )
    (net (code "48") (name "Net-(U35-CP2)") (class "Default")
      (node (ref "C90") (pin "2") (pinfunction "2_2") (pintype "passive"))
      (node (ref "U35") (pin "10") (pinfunction "CP2_10") (pintype "passive"))
    )
    (net (code "49") (name "Net-(U35-GHA)") (class "Default")
      (node (ref "R99") (pin "1") (pinfunction "1_1") (pintype "passive"))
      (node (ref "U35") (pin "21") (pinfunction "GHA_21") (pintype "passive"))
    )
    (net (code "50") (name "Net-(U35-GHB)") (class "Default")
      (node (ref "R102") (pin "1") (pinfunction "1_1") (pintype "passive"))
      (node (ref "U35") (pin "19") (pinfunction "GHB_19") (pintype "passive"))
    )
    (net (code "51") (name "Net-(U35-GHC)") (class "Default")
      (node (ref "R103") (pin "1") (pinfunction "1_1") (pintype "passive"))
      (node (ref "U35") (pin "17") (pinfunction "GHC_17") (pintype "passive"))
    )
    (net (code "52") (name "Net-(U35-HA-)") (class "Default")
      (node (ref "R100") (pin "1") (pinfunction "1_1") (pintype "passive"))
      (node (ref "R101") (pin "1") (pinfunction "1_1") (pintype "passive"))
      (node (ref "U35") (pin "2") (pinfunction "HA-_2") (pintype "passive"))
      (node (ref "U35") (pin "4") (pinfunction "HB-_4") (pintype "passive"))
      (node (ref "U35") (pin "6") (pinfunction "HC-_6") (pintype "passive"))
    )
    (net (code "53") (name "Net-(U35-HBIAS)") (class "Default")
      (node (ref "C91") (pin "2") (pinfunction "2_2") (pintype "passive"))
      (node (ref "R101") (pin "2") (pinfunction "2_2") (pintype "passive"))
      (node (ref "U35") (pin "8") (pinfunction "HBIAS_8") (pintype "passive"))
    )
    (net (code "54") (name "Net-(U35-SENSE)") (class "Default")
      (node (ref "C96") (pin "1") (pinfunction "1_1") (pintype "passive"))
      (node (ref "R106") (pin "1") (pinfunction "1_1") (pintype "passive"))
      (node (ref "U35") (pin "13") (pinfunction "SENSE_13") (pintype "passive"))
    )
    (net (code "55") (name "Net-(U35-VCP)") (class "Default")
      (node (ref "C92") (pin "1") (pinfunction "1_1") (pintype "passive"))
      (node (ref "U35") (pin "12") (pinfunction "VCP_12") (pintype "passive"))
    )
    (net (code "56") (name "Net-(U38-GND4)") (class "Default")
      (node (ref "R116") (pin "2") (pinfunction "2_2") (pintype "passive"))
      (node (ref "U38") (pin "17") (pinfunction "GND4_17") (pintype "passive"))
    )
    (net (code "57") (name "Net-(U38-LED0{slash}GPIO3)") (class "Default")
      (node (ref "R115") (pin "1") (pinfunction "1_1") (pintype "passive"))
      (node (ref "U38") (pin "13") (pinfunction "LED0/GPIO3_13") (pintype "passive"))
    )
    (net (code "58") (name "Net-(U38-LED1{slash}GPIO4)") (class "Default")
      (node (ref "R114") (pin "1") (pinfunction "1_1") (pintype "passive"))
      (node (ref "U38") (pin "14") (pinfunction "LED1/GPIO4_14") (pintype "passive"))
    )
    (net (code "59") (name "Net-(U38-VBUS)") (class "Default")
      (node (ref "TP52") (pin "1") (pinfunction "1_1") (pintype "passive"))
      (node (ref "U38") (pin "28") (pinfunction "VBUS_28") (pintype "passive"))
    )
    (net (code "60") (name "Net-(U39-BYPASS)") (class "Default")
      (node (ref "C101") (pin "1") (pinfunction "1_1") (pintype "passive"))
      (node (ref "U39") (pin "2") (pinfunction "BYPASS_2") (pintype "passive"))
    )
    (net (code "61") (name "Net-(U39-IN+)") (class "Default")
      (node (ref "R118") (pin "1") (pinfunction "1_1") (pintype "passive"))
      (node (ref "U39") (pin "4") (pinfunction "IN+_4") (pintype "passive"))
    )
    (net (code "62") (name "Net-(U39-IN-)") (class "Default")
      (node (ref "R117") (pin "1") (pinfunction "1_1") (pintype "passive"))
      (node (ref "U39") (pin "3") (pinfunction "IN-_3") (pintype "passive"))
    )
    (net (code "63") (name "Net-(U39-OUT+)") (class "Default")
      (node (ref "FB3") (pin "1") (pinfunction "1_1") (pintype "passive"))
      (node (ref "U39") (pin "5") (pinfunction "OUT+_5") (pintype "passive"))
    )
    (net (code "64") (name "Net-(U39-OUT-)") (class "Default")
      (node (ref "FB2") (pin "1") (pinfunction "1_1") (pintype "passive"))
      (node (ref "U39") (pin "8") (pinfunction "OUT-_8") (pintype "passive"))
    )
    (net (code "65") (name "Net-(U40-BYPASS)") (class "Default")
      (node (ref "C106") (pin "1") (pinfunction "1_1") (pintype "passive"))
      (node (ref "U40") (pin "2") (pinfunction "BYPASS_2") (pintype "passive"))
    )
    (net (code "66") (name "Net-(U40-IN+)") (class "Default")
      (node (ref "R121") (pin "1") (pinfunction "1_1") (pintype "passive"))
      (node (ref "U40") (pin "4") (pinfunction "IN+_4") (pintype "passive"))
    )
    (net (code "67") (name "Net-(U40-IN-)") (class "Default")
      (node (ref "R123") (pin "1") (pinfunction "1_1") (pintype "passive"))
      (node (ref "U40") (pin "3") (pinfunction "IN-_3") (pintype "passive"))
    )
    (net (code "68") (name "Net-(U40-OUT+)") (class "Default")
      (node (ref "FB5") (pin "1") (pinfunction "1_1") (pintype "passive"))
      (node (ref "U40") (pin "5") (pinfunction "OUT+_5") (pintype "passive"))
    )
    (net (code "69") (name "Net-(U40-OUT-)") (class "Default")
      (node (ref "FB4") (pin "1") (pinfunction "1_1") (pintype "passive"))
      (node (ref "U40") (pin "8") (pinfunction "OUT-_8") (pintype "passive"))
    )
    (net (code "70") (name "PREV") (class "Default")
      (node (ref "R112") (pin "2") (pinfunction "2_2") (pintype "passive"))
      (node (ref "U38") (pin "7") (pinfunction "PREV/TDI_7") (pintype "passive"))
    )
    (net (code "71") (name "RSTN") (class "Default")
      (node (ref "Q19") (pin "3") (pinfunction "C_3") (pintype "passive"))
      (node (ref "R119") (pin "2") (pinfunction "2_2") (pintype "passive"))
      (node (ref "U38") (pin "8") (pinfunction "RSTN_8") (pintype "passive"))
    )
    (net (code "72") (name "VBAT") (class "Default")
      (node (ref "U36") (pin "2") (pinfunction "2_2") (pintype "passive"))
    )
    (net (code "73") (name "VOL+") (class "Default")
      (node (ref "R109") (pin "2") (pinfunction "2_2") (pintype "passive"))
      (node (ref "U38") (pin "4") (pinfunction "VOL+/TMS_4") (pintype "passive"))
    )
    (net (code "74") (name "VOL-") (class "Default")
      (node (ref "R110") (pin "2") (pinfunction "2_2") (pintype "passive"))
      (node (ref "U38") (pin "5") (pinfunction "VOL-/TCK_5") (pintype "passive"))
    )
    (net (code "75") (name "unconnected-(RP15-Pad4)") (class "Default")
      (node (ref "RP15") (pin "4") (pinfunction "4_4") (pintype "passive+no_connect"))
    )
    (net (code "76") (name "unconnected-(RP15-Pad5)") (class "Default")
      (node (ref "RP15") (pin "5") (pinfunction "5_5") (pintype "passive+no_connect"))
    )
    (net (code "77") (name "unconnected-(RP16-Pad4)") (class "Default")
      (node (ref "RP16") (pin "4") (pinfunction "4_4") (pintype "passive+no_connect"))
    )
    (net (code "78") (name "unconnected-(RP16-Pad5)") (class "Default")
      (node (ref "RP16") (pin "5") (pinfunction "5_5") (pintype "passive+no_connect"))
    )
    (net (code "79") (name "unconnected-(U35-FG1-Pad23)") (class "Default")
      (node (ref "U35") (pin "23") (pinfunction "FG1_23") (pintype "passive+no_connect"))
    )
    (net (code "80") (name "unconnected-(U35-FG2-Pad24)") (class "Default")
      (node (ref "U35") (pin "24") (pinfunction "FG2_24") (pintype "passive+no_connect"))
    )
    (net (code "81") (name "unconnected-(U38-3V_OUT-Pad30)") (class "Default")
      (node (ref "U38") (pin "30") (pinfunction "3V_OUT_30") (pintype "passive+no_connect"))
    )
    (net (code "82") (name "unconnected-(U38-ANT-Pad2)") (class "Default")
      (node (ref "U38") (pin "2") (pinfunction "ANT_2") (pintype "passive+no_connect"))
    )
    (net (code "83") (name "unconnected-(U38-AUXL-Pad20)") (class "Default")
      (node (ref "U38") (pin "20") (pinfunction "AUXL_20") (pintype "passive+no_connect"))
    )
    (net (code "84") (name "unconnected-(U38-AUXR-Pad19)") (class "Default")
      (node (ref "U38") (pin "19") (pinfunction "AUXR_19") (pintype "passive+no_connect"))
    )
    (net (code "85") (name "unconnected-(U38-AUX_DET{slash}GPIO11-Pad18)") (class "Default")
      (node (ref "U38") (pin "18") (pinfunction "AUX_DET/GPIO11_18") (pintype "passive+no_connect"))
    )
    (net (code "86") (name "unconnected-(U38-GND2-Pad3)") (class "Default")
      (node (ref "U38") (pin "3") (pinfunction "GND2_3") (pintype "passive+no_connect"))
    )
    (net (code "87") (name "unconnected-(U38-MBISTEN-Pad9)") (class "Default")
      (node (ref "U38") (pin "9") (pinfunction "MBISTEN_9") (pintype "passive+no_connect"))
    )
    (net (code "88") (name "unconnected-(U38-MICN-Pad21)") (class "Default")
      (node (ref "U38") (pin "21") (pinfunction "MICN_21") (pintype "passive+no_connect"))
    )
    (net (code "89") (name "unconnected-(U38-MICP-Pad22)") (class "Default")
      (node (ref "U38") (pin "22") (pinfunction "MICP_22") (pintype "passive+no_connect"))
    )
    (net (code "90") (name "unconnected-(U38-P_P{slash}CALL{slash}GPIO2-Pad12)") (class "Default")
      (node (ref "U38") (pin "12") (pinfunction "P_P/CALL/GPIO2_12") (pintype "passive+no_connect"))
    )
    (net (code "91") (name "unconnected-(U38-VADC-Pad31)") (class "Default")
      (node (ref "U38") (pin "31") (pinfunction "VADC_31") (pintype "passive+no_connect"))
    )
    (net (code "92") (name "unconnected-(U38-VMIC-Pad23)") (class "Default")
      (node (ref "U38") (pin "23") (pinfunction "VMIC_23") (pintype "passive+no_connect"))
    )
  )
)
